# emetteurRG.net
KiCad netlist of a schematic drawn in EAGLE
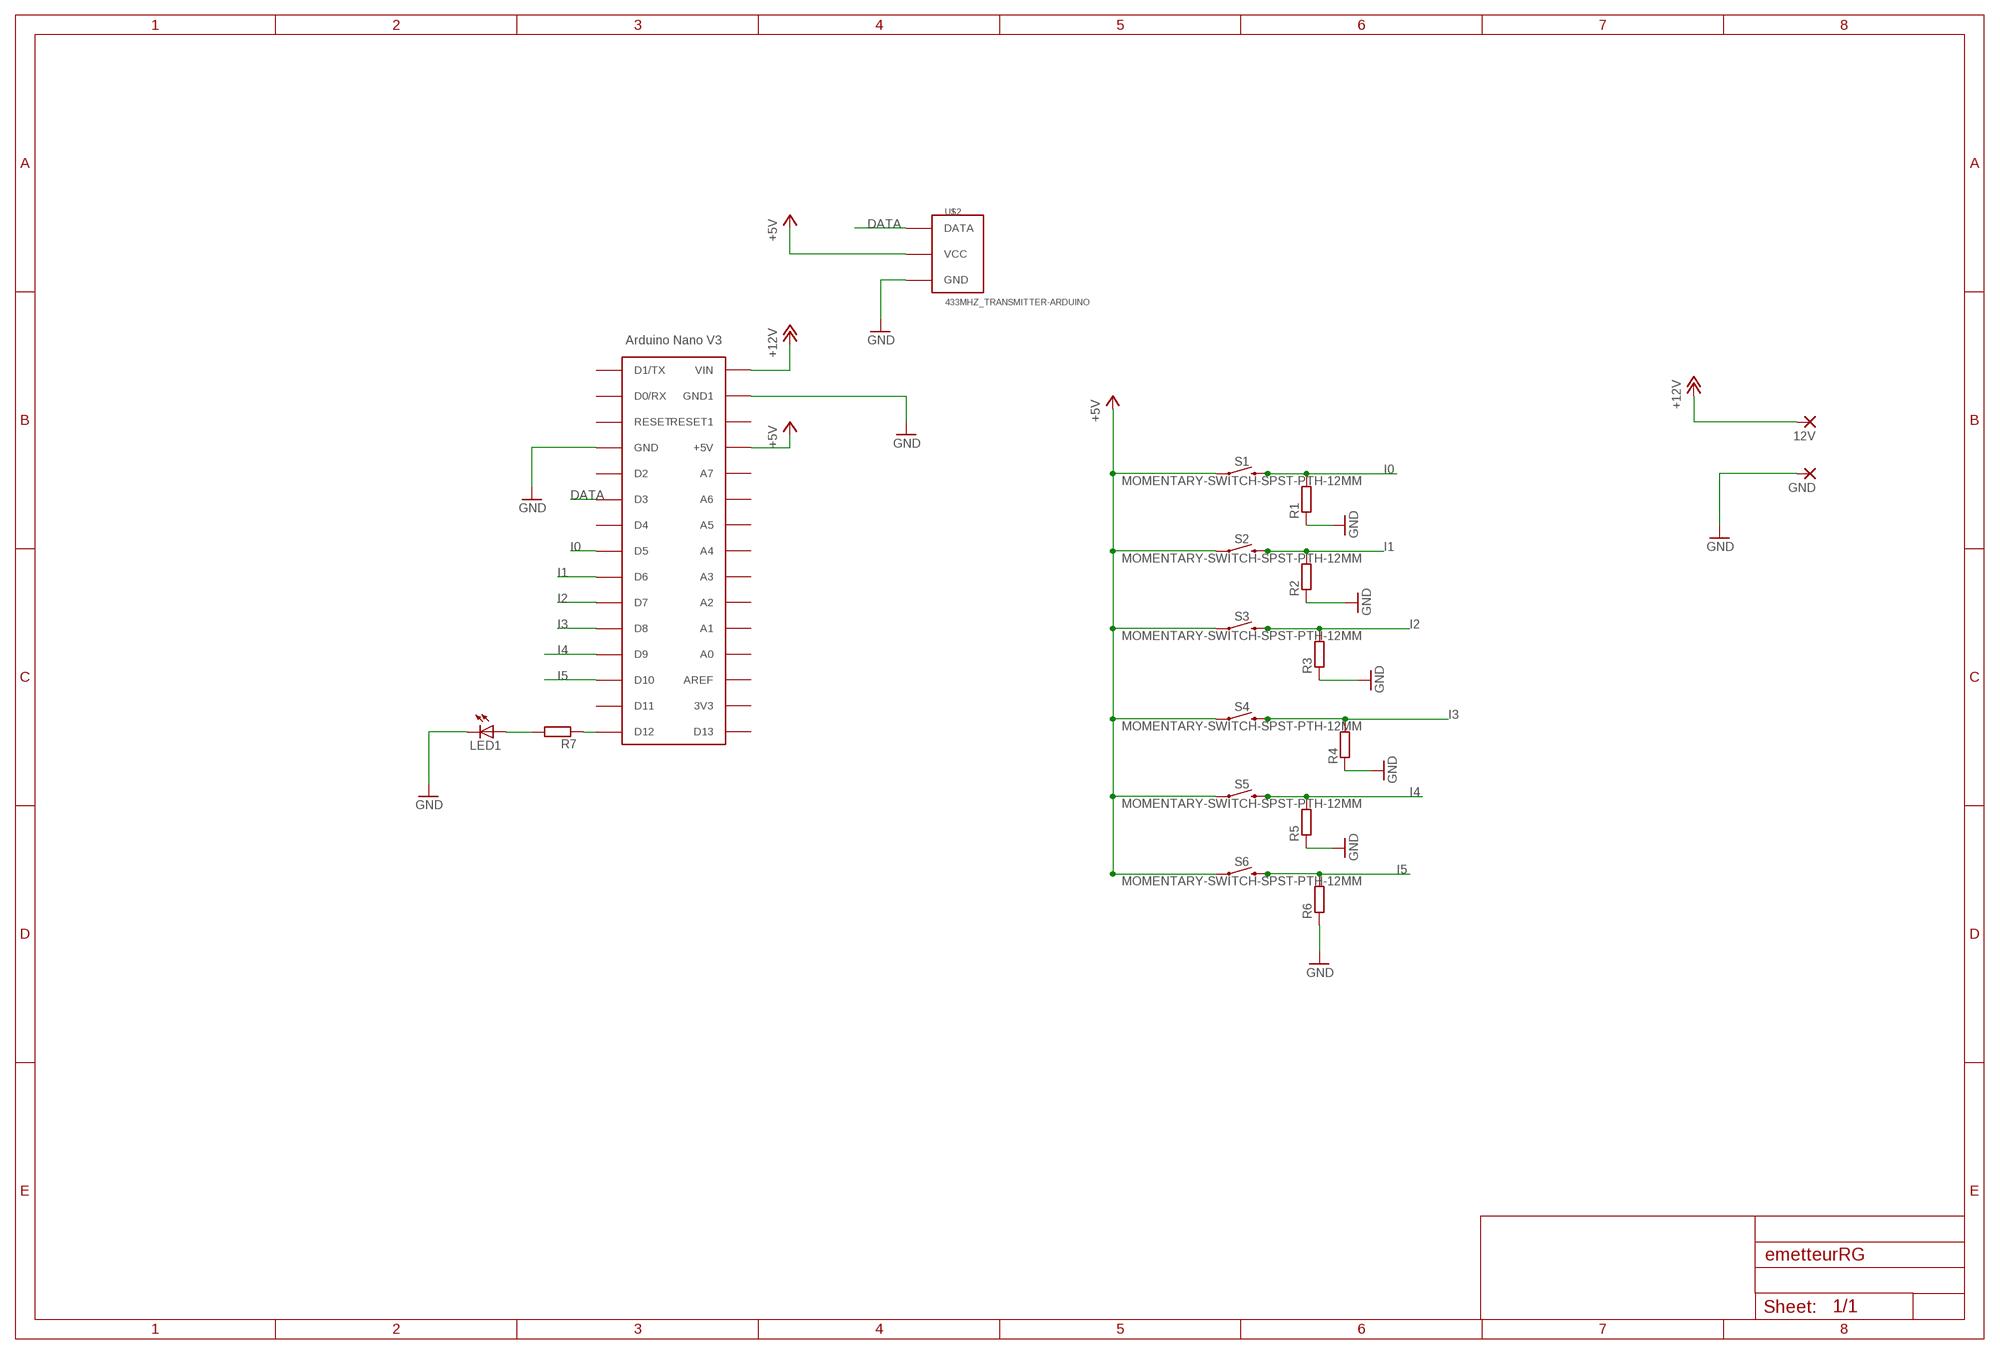
[diagram p0: schematic, sheet 1]

(export (version "E")
  (design (tool "Eeschema 10.0.6"))
  (components
    (comp (ref "12V")
      (value "SMD5")
      (footprint "eagle-import:SMD2,54-5,08")
      (libsource (lib "eagle-import") (part "SMD5"))
    )
    (comp (ref "GND")
      (value "SMD5")
      (footprint "eagle-import:SMD2,54-5,08")
      (libsource (lib "eagle-import") (part "SMD5"))
    )
    (comp (ref "LED1")
      (value "LED5MM")
      (footprint "eagle-import:LED5MM")
      (libsource (lib "eagle-import") (part "LED5MM"))
    )
    (comp (ref "R1")
      (value "R-EU_R1206")
      (footprint "eagle-import:R1206")
      (libsource (lib "eagle-import") (part "R-EU_R1206"))
    )
    (comp (ref "R2")
      (value "R-EU_R1206")
      (footprint "eagle-import:R1206")
      (libsource (lib "eagle-import") (part "R-EU_R1206"))
    )
    (comp (ref "R3")
      (value "R-EU_R1206")
      (footprint "eagle-import:R1206")
      (libsource (lib "eagle-import") (part "R-EU_R1206"))
    )
    (comp (ref "R4")
      (value "R-EU_R1206")
      (footprint "eagle-import:R1206")
      (libsource (lib "eagle-import") (part "R-EU_R1206"))
    )
    (comp (ref "R5")
      (value "R-EU_R1206")
      (footprint "eagle-import:R1206")
      (libsource (lib "eagle-import") (part "R-EU_R1206"))
    )
    (comp (ref "R6")
      (value "R-EU_R1206")
      (footprint "eagle-import:R1206")
      (libsource (lib "eagle-import") (part "R-EU_R1206"))
    )
    (comp (ref "R7")
      (value "R-EU_R1206")
      (footprint "eagle-import:R1206")
      (libsource (lib "eagle-import") (part "R-EU_R1206"))
    )
    (comp (ref "S1")
      (value "MOMENTARY-SWITCH-SPST-PTH-12MM")
      (footprint "eagle-import:TACTILE_SWITCH_PTH_12MM")
      (libsource (lib "eagle-import") (part "MOMENTARY-SWITCH-SPST-PTH-12MM"))
    )
    (comp (ref "S2")
      (value "MOMENTARY-SWITCH-SPST-PTH-12MM")
      (footprint "eagle-import:TACTILE_SWITCH_PTH_12MM")
      (libsource (lib "eagle-import") (part "MOMENTARY-SWITCH-SPST-PTH-12MM"))
    )
    (comp (ref "S3")
      (value "MOMENTARY-SWITCH-SPST-PTH-12MM")
      (footprint "eagle-import:TACTILE_SWITCH_PTH_12MM")
      (libsource (lib "eagle-import") (part "MOMENTARY-SWITCH-SPST-PTH-12MM"))
    )
    (comp (ref "S4")
      (value "MOMENTARY-SWITCH-SPST-PTH-12MM")
      (footprint "eagle-import:TACTILE_SWITCH_PTH_12MM")
      (libsource (lib "eagle-import") (part "MOMENTARY-SWITCH-SPST-PTH-12MM"))
    )
    (comp (ref "S5")
      (value "MOMENTARY-SWITCH-SPST-PTH-12MM")
      (footprint "eagle-import:TACTILE_SWITCH_PTH_12MM")
      (libsource (lib "eagle-import") (part "MOMENTARY-SWITCH-SPST-PTH-12MM"))
    )
    (comp (ref "S6")
      (value "MOMENTARY-SWITCH-SPST-PTH-12MM")
      (footprint "eagle-import:TACTILE_SWITCH_PTH_12MM")
      (libsource (lib "eagle-import") (part "MOMENTARY-SWITCH-SPST-PTH-12MM"))
    )
    (comp (ref "U$1")
      (value "ARDUINONANO")
      (footprint "eagle-import:PDIP-32")
      (libsource (lib "eagle-import") (part "ARDUINONANO"))
    )
    (comp (ref "U$2")
      (value "433MHZ_TRANSMITTER-ARDUINO")
      (footprint "eagle-import:433MHZ_TRANSMITTER-ARDUINO")
      (libsource (lib "eagle-import") (part "433MHZ_TRANSMITTER-ARDUINO"))
    )
  )
  (nets
    (net (code "1") (name "+5V") (class "Default")
      (node (ref "S1") (pin "1") (pinfunction "1_1") (pintype "passive"))
      (node (ref "S2") (pin "1") (pinfunction "1_1") (pintype "passive"))
      (node (ref "S3") (pin "1") (pinfunction "1_1") (pintype "passive"))
      (node (ref "S4") (pin "1") (pinfunction "1_1") (pintype "passive"))
      (node (ref "S5") (pin "1") (pinfunction "1_1") (pintype "passive"))
      (node (ref "S6") (pin "1") (pinfunction "1_1") (pintype "passive"))
      (node (ref "U$1") (pin "+5V") (pinfunction "+5V_+5V") (pintype "bidirectional"))
      (node (ref "U$2") (pin "VCC") (pinfunction "VCC_VCC") (pintype "bidirectional"))
    )
    (net (code "2") (name "+12V") (class "Default")
      (node (ref "12V") (pin "1") (pinfunction "P_1") (pintype "passive"))
      (node (ref "U$1") (pin "VIN") (pinfunction "VIN_VIN") (pintype "bidirectional"))
    )
    (net (code "3") (name "/DATA") (class "Default")
      (node (ref "U$1") (pin "D3") (pinfunction "D3_D3") (pintype "bidirectional"))
      (node (ref "U$2") (pin "DATA") (pinfunction "DATA_DATA") (pintype "bidirectional"))
    )
    (net (code "4") (name "/I0") (class "Default")
      (node (ref "R1") (pin "2") (pinfunction "2_2") (pintype "passive"))
      (node (ref "S1") (pin "3") (pinfunction "2_3") (pintype "passive"))
      (node (ref "U$1") (pin "D5") (pinfunction "D5_D5") (pintype "bidirectional"))
    )
    (net (code "5") (name "/I1") (class "Default")
      (node (ref "R2") (pin "2") (pinfunction "2_2") (pintype "passive"))
      (node (ref "S2") (pin "3") (pinfunction "2_3") (pintype "passive"))
      (node (ref "U$1") (pin "D6") (pinfunction "D6_D6") (pintype "bidirectional"))
    )
    (net (code "6") (name "/I2") (class "Default")
      (node (ref "R3") (pin "2") (pinfunction "2_2") (pintype "passive"))
      (node (ref "S3") (pin "3") (pinfunction "2_3") (pintype "passive"))
      (node (ref "U$1") (pin "D7") (pinfunction "D7_D7") (pintype "bidirectional"))
    )
    (net (code "7") (name "/I3") (class "Default")
      (node (ref "R4") (pin "2") (pinfunction "2_2") (pintype "passive"))
      (node (ref "S4") (pin "3") (pinfunction "2_3") (pintype "passive"))
      (node (ref "U$1") (pin "D8") (pinfunction "D8_D8") (pintype "bidirectional"))
    )
    (net (code "8") (name "/I4") (class "Default")
      (node (ref "R5") (pin "2") (pinfunction "2_2") (pintype "passive"))
      (node (ref "S5") (pin "3") (pinfunction "2_3") (pintype "passive"))
      (node (ref "U$1") (pin "D9") (pinfunction "D9_D9") (pintype "bidirectional"))
    )
    (net (code "9") (name "/I5") (class "Default")
      (node (ref "R6") (pin "2") (pinfunction "2_2") (pintype "passive"))
      (node (ref "S6") (pin "3") (pinfunction "2_3") (pintype "passive"))
      (node (ref "U$1") (pin "D10") (pinfunction "D10_D10") (pintype "bidirectional"))
    )
    (net (code "10") (name "GND") (class "Default")
      (node (ref "GND") (pin "1") (pinfunction "P_1") (pintype "passive"))
      (node (ref "LED1") (pin "K") (pinfunction "C_K") (pintype "passive"))
      (node (ref "R1") (pin "1") (pinfunction "1_1") (pintype "passive"))
      (node (ref "R2") (pin "1") (pinfunction "1_1") (pintype "passive"))
      (node (ref "R3") (pin "1") (pinfunction "1_1") (pintype "passive"))
      (node (ref "R4") (pin "1") (pinfunction "1_1") (pintype "passive"))
      (node (ref "R5") (pin "1") (pinfunction "1_1") (pintype "passive"))
      (node (ref "R6") (pin "1") (pinfunction "1_1") (pintype "passive"))
      (node (ref "U$1") (pin "GND") (pinfunction "GND_GND") (pintype "bidirectional"))
      (node (ref "U$1") (pin "GND1") (pinfunction "GND1_GND1") (pintype "bidirectional"))
      (node (ref "U$2") (pin "GND") (pinfunction "GND_GND") (pintype "bidirectional"))
    )
    (net (code "11") (name "Net-(LED1-PadA)") (class "Default")
      (node (ref "LED1") (pin "A") (pinfunction "A_A") (pintype "passive"))
      (node (ref "R7") (pin "2") (pinfunction "2_2") (pintype "passive"))
    )
    (net (code "12") (name "Net-(R7-Pad1)") (class "Default")
      (node (ref "R7") (pin "1") (pinfunction "1_1") (pintype "passive"))
      (node (ref "U$1") (pin "D12") (pinfunction "D12_D12") (pintype "bidirectional"))
    )
    (net (code "13") (name "unconnected-(U$1-A0-PadA7)") (class "Default")
      (node (ref "U$1") (pin "A7") (pinfunction "A0_A7") (pintype "bidirectional"))
    )
    (net (code "14") (name "unconnected-(U$1-A1-PadA6)") (class "Default")
      (node (ref "U$1") (pin "A6") (pinfunction "A1_A6") (pintype "bidirectional"))
    )
    (net (code "15") (name "unconnected-(U$1-A2-PadA5)") (class "Default")
      (node (ref "U$1") (pin "A5") (pinfunction "A2_A5") (pintype "bidirectional"))
    )
    (net (code "16") (name "unconnected-(U$1-A3-PadA4)") (class "Default")
      (node (ref "U$1") (pin "A4") (pinfunction "A3_A4") (pintype "bidirectional"))
    )
    (net (code "17") (name "unconnected-(U$1-A4-PadA3)") (class "Default")
      (node (ref "U$1") (pin "A3") (pinfunction "A4_A3") (pintype "bidirectional"))
    )
    (net (code "18") (name "unconnected-(U$1-A5-PadA2)") (class "Default")
      (node (ref "U$1") (pin "A2") (pinfunction "A5_A2") (pintype "bidirectional"))
    )
    (net (code "19") (name "unconnected-(U$1-A6-PadA1)") (class "Default")
      (node (ref "U$1") (pin "A1") (pinfunction "A6_A1") (pintype "bidirectional"))
    )
    (net (code "20") (name "unconnected-(U$1-A7-PadA0)") (class "Default")
      (node (ref "U$1") (pin "A0") (pinfunction "A7_A0") (pintype "bidirectional"))
    )
    (net (code "21") (name "unconnected-(U$1-Pad3V3)") (class "Default")
      (node (ref "U$1") (pin "3V3") (pinfunction "3V3_3V3") (pintype "bidirectional"))
    )
    (net (code "22") (name "unconnected-(U$1-PadAREF)") (class "Default")
      (node (ref "U$1") (pin "AREF") (pinfunction "AREF_AREF") (pintype "bidirectional"))
    )
    (net (code "23") (name "unconnected-(U$1-PadD0{slash}RX)") (class "Default")
      (node (ref "U$1") (pin "D0/RX") (pinfunction "D0/RX_D0/RX") (pintype "bidirectional"))
    )
    (net (code "24") (name "unconnected-(U$1-PadD1{slash}TX)") (class "Default")
      (node (ref "U$1") (pin "D1/TX") (pinfunction "D1/TX_D1/TX") (pintype "bidirectional"))
    )
    (net (code "25") (name "unconnected-(U$1-PadD2)") (class "Default")
      (node (ref "U$1") (pin "D2") (pinfunction "D2_D2") (pintype "bidirectional"))
    )
    (net (code "26") (name "unconnected-(U$1-PadD4)") (class "Default")
      (node (ref "U$1") (pin "D4") (pinfunction "D4_D4") (pintype "bidirectional"))
    )
    (net (code "27") (name "unconnected-(U$1-PadD11)") (class "Default")
      (node (ref "U$1") (pin "D11") (pinfunction "D11_D11") (pintype "bidirectional"))
    )
    (net (code "28") (name "unconnected-(U$1-PadD13)") (class "Default")
      (node (ref "U$1") (pin "D13") (pinfunction "D13_D13") (pintype "bidirectional"))
    )
    (net (code "29") (name "unconnected-(U$1-PadRESET)") (class "Default")
      (node (ref "U$1") (pin "RESET") (pinfunction "RESET_RESET") (pintype "bidirectional"))
    )
    (net (code "30") (name "unconnected-(U$1-PadRESET1)") (class "Default")
      (node (ref "U$1") (pin "RESET1") (pinfunction "RESET1_RESET1") (pintype "bidirectional"))
    )
  )
)
